# axiom_beta_plugin_module_1xHDMI_v0_6_b41.net
KiCad netlist of a schematic drawn in EAGLE
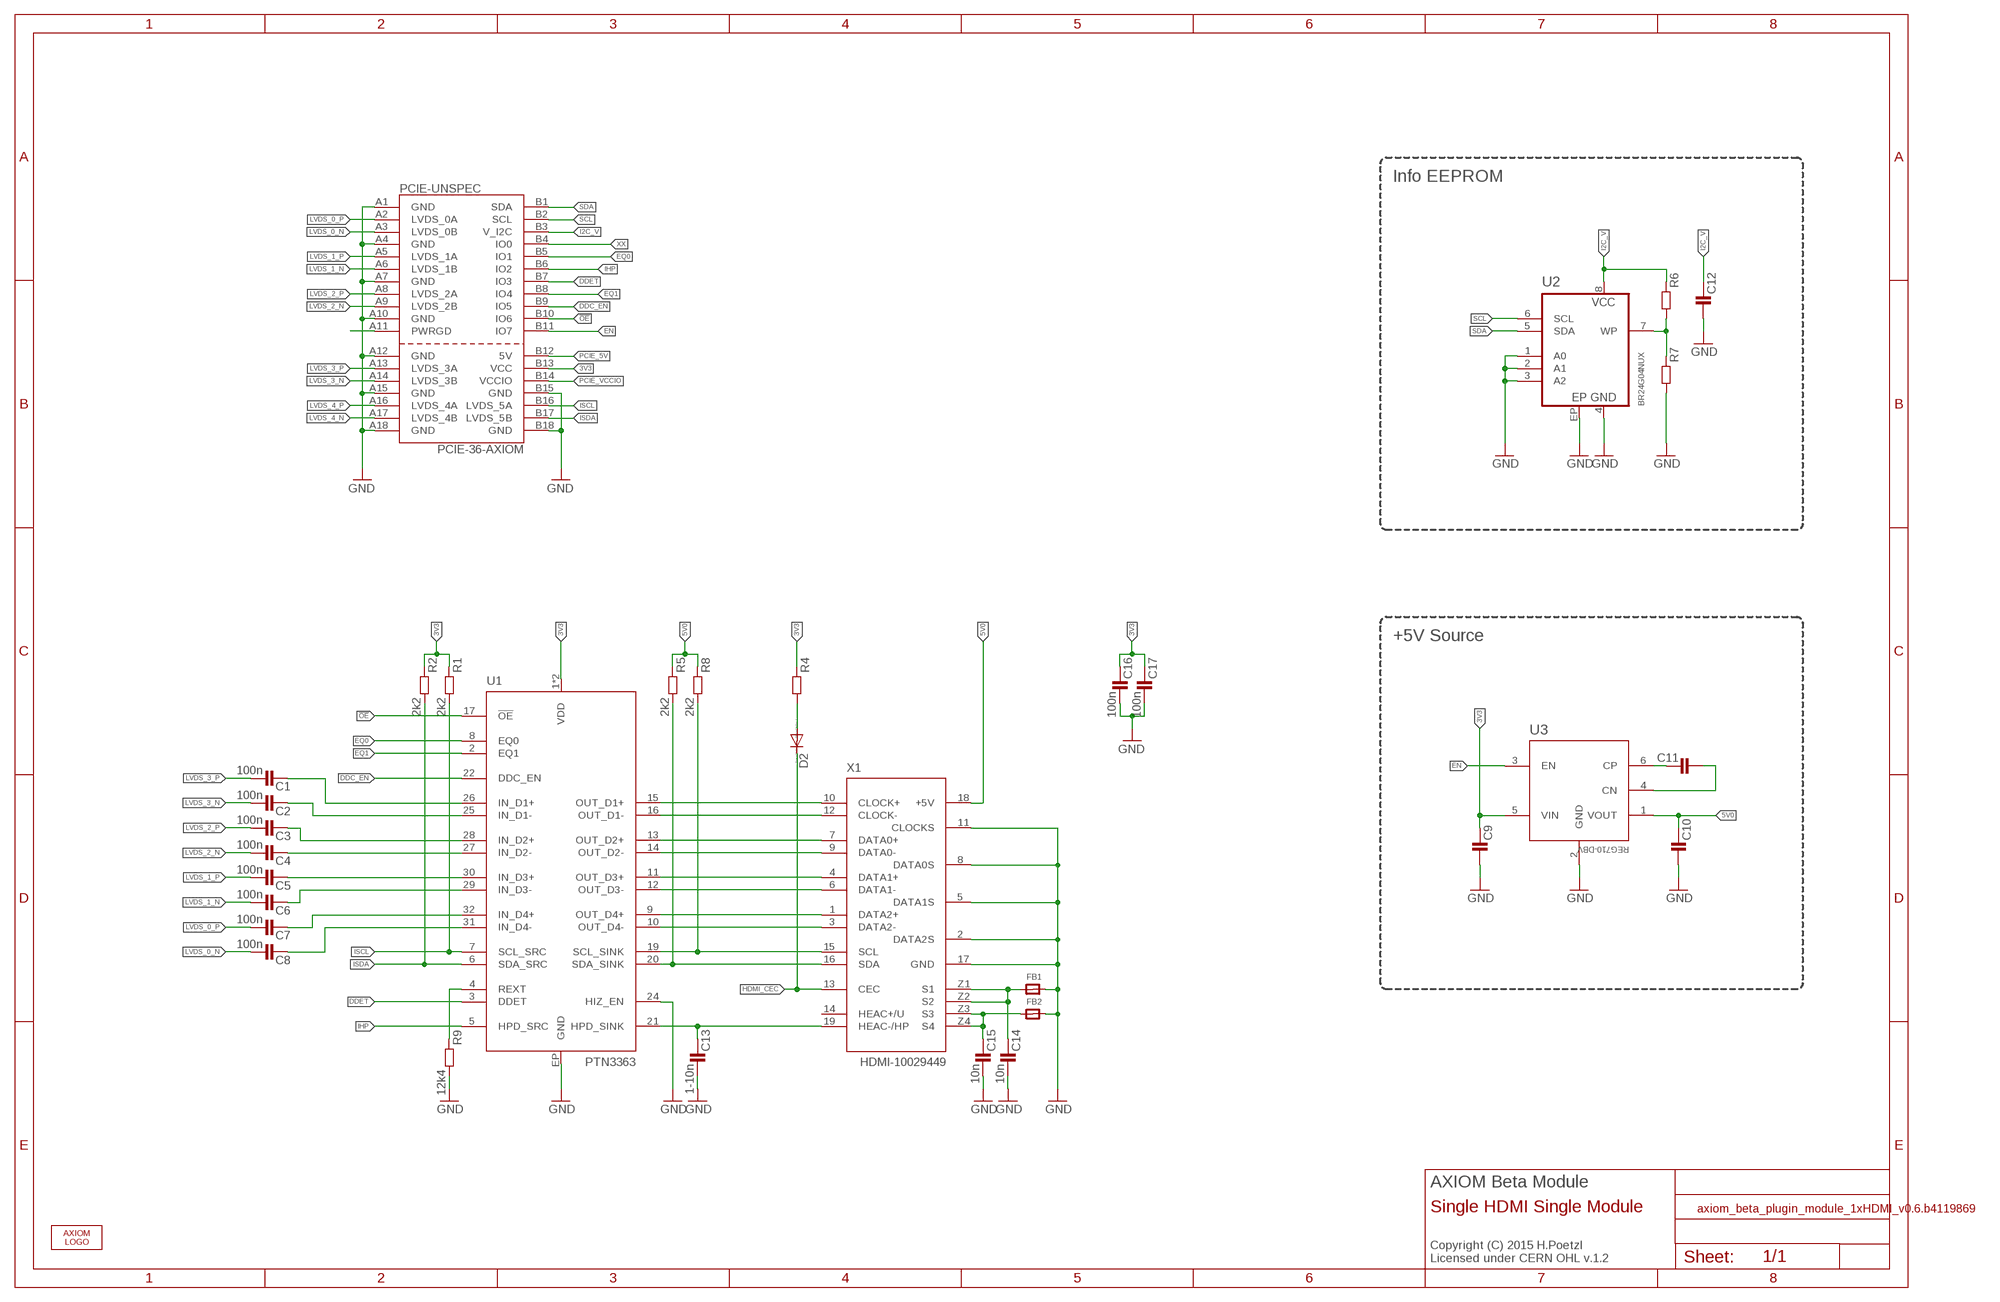
[diagram p0: schematic, sheet 1]

(export (version "E")
  (design (tool "Eeschema 10.0.6"))
  (components
    (comp (ref "C1")
      (value "100n")
      (footprint "eagle-import:0402-C")
      (libsource (lib "eagle-import") (part "C0402-C"))
    )
    (comp (ref "C2")
      (value "100n")
      (footprint "eagle-import:0402-C")
      (libsource (lib "eagle-import") (part "C0402-C"))
    )
    (comp (ref "C3")
      (value "100n")
      (footprint "eagle-import:0402-C")
      (libsource (lib "eagle-import") (part "C0402-C"))
    )
    (comp (ref "C4")
      (value "100n")
      (footprint "eagle-import:0402-C")
      (libsource (lib "eagle-import") (part "C0402-C"))
    )
    (comp (ref "C5")
      (value "100n")
      (footprint "eagle-import:0402-C")
      (libsource (lib "eagle-import") (part "C0402-C"))
    )
    (comp (ref "C6")
      (value "100n")
      (footprint "eagle-import:0402-C")
      (libsource (lib "eagle-import") (part "C0402-C"))
    )
    (comp (ref "C7")
      (value "100n")
      (footprint "eagle-import:0402-C")
      (libsource (lib "eagle-import") (part "C0402-C"))
    )
    (comp (ref "C8")
      (value "100n")
      (footprint "eagle-import:0402-C")
      (libsource (lib "eagle-import") (part "C0402-C"))
    )
    (comp (ref "C9")
      (value "C0603-B")
      (footprint "eagle-import:0603-B")
      (libsource (lib "eagle-import") (part "C0603-B"))
    )
    (comp (ref "C10")
      (value "C0603-B")
      (footprint "eagle-import:0603-B")
      (libsource (lib "eagle-import") (part "C0603-B"))
    )
    (comp (ref "C11")
      (value "C0603-B")
      (footprint "eagle-import:0603-B")
      (libsource (lib "eagle-import") (part "C0603-B"))
    )
    (comp (ref "C12")
      (value "C0402-B")
      (footprint "eagle-import:0402-B")
      (libsource (lib "eagle-import") (part "C0402-B"))
    )
    (comp (ref "C13")
      (value "1-10n")
      (footprint "eagle-import:0402-B")
      (libsource (lib "eagle-import") (part "C0402-B"))
    )
    (comp (ref "C14")
      (value "10n")
      (footprint "eagle-import:0402-B")
      (libsource (lib "eagle-import") (part "C0402-B"))
    )
    (comp (ref "C15")
      (value "10n")
      (footprint "eagle-import:0402-B")
      (libsource (lib "eagle-import") (part "C0402-B"))
    )
    (comp (ref "C16")
      (value "100n")
      (footprint "eagle-import:0402-B")
      (libsource (lib "eagle-import") (part "C0402-B"))
    )
    (comp (ref "C17")
      (value "100n")
      (footprint "eagle-import:0402-B")
      (libsource (lib "eagle-import") (part "C0402-B"))
    )
    (comp (ref "D2")
      (value "DIODE-SOD523")
      (footprint "eagle-import:SOD523")
      (libsource (lib "eagle-import") (part "DIODE-SOD523"))
    )
    (comp (ref "FB1")
      (value "FERRITE_0603MP")
      (footprint "eagle-import:_0603MP")
      (libsource (lib "eagle-import") (part "FERRITE_0603MP"))
    )
    (comp (ref "FB2")
      (value "FERRITE_0603MP")
      (footprint "eagle-import:_0603MP")
      (libsource (lib "eagle-import") (part "FERRITE_0603MP"))
    )
    (comp (ref "PCIE-UNSPEC")
      (value "PCIE-36-AXIOM")
      (footprint "eagle-import:PCIE-36-AXIOM")
      (libsource (lib "eagle-import") (part "PCIE-36-AXIOM"))
    )
    (comp (ref "R1")
      (value "2k2")
      (footprint "eagle-import:0402-B")
      (libsource (lib "eagle-import") (part "R0402-B"))
    )
    (comp (ref "R2")
      (value "2k2")
      (footprint "eagle-import:0402-B")
      (libsource (lib "eagle-import") (part "R0402-B"))
    )
    (comp (ref "R4")
      (value "R0402-B")
      (footprint "eagle-import:0402-B")
      (libsource (lib "eagle-import") (part "R0402-B"))
    )
    (comp (ref "R5")
      (value "2k2")
      (footprint "eagle-import:0402-B")
      (libsource (lib "eagle-import") (part "R0402-B"))
    )
    (comp (ref "R6")
      (value "R0402-B")
      (footprint "eagle-import:0402-B")
      (libsource (lib "eagle-import") (part "R0402-B"))
    )
    (comp (ref "R7")
      (value "R0402-B")
      (footprint "eagle-import:0402-B")
      (libsource (lib "eagle-import") (part "R0402-B"))
    )
    (comp (ref "R8")
      (value "2k2")
      (footprint "eagle-import:0402-B")
      (libsource (lib "eagle-import") (part "R0402-B"))
    )
    (comp (ref "R9")
      (value "12k4")
      (footprint "eagle-import:0402-B")
      (libsource (lib "eagle-import") (part "R0402-B"))
    )
    (comp (ref "U$1")
      (value "AXIOM_LOGO459X70")
      (footprint "eagle-import:AXIOM_LOGO_459X70")
      (libsource (lib "eagle-import") (part "AXIOM_LOGO459X70"))
    )
    (comp (ref "U1")
      (value "PTN3363")
      (footprint "eagle-import:HVQFN32")
      (libsource (lib "eagle-import") (part "PTN3363"))
    )
    (comp (ref "U2")
      (value "BR24G04NUX")
      (footprint "eagle-import:DFN200X300X100-9N")
      (libsource (lib "eagle-import") (part "BR24G04NUX"))
    )
    (comp (ref "U3")
      (value "REG710-DBV")
      (footprint "eagle-import:DBV")
      (libsource (lib "eagle-import") (part "REG710-DBV"))
    )
    (comp (ref "X1")
      (value "HDMI-10029449")
      (footprint "eagle-import:10029449-X01XLF")
      (libsource (lib "eagle-import") (part "HDMI-10029449"))
    )
  )
  (nets
    (net (code "1") (name "/~{OE}") (class "Default")
      (node (ref "PCIE-UNSPEC") (pin "B10") (pinfunction "IO6_B10") (pintype "passive"))
      (node (ref "U1") (pin "17") (pinfunction "~{OE}_17") (pintype "bidirectional"))
    )
    (net (code "2") (name "3V3") (class "Default")
      (node (ref "C16") (pin "1") (pinfunction "1_1") (pintype "passive"))
      (node (ref "C17") (pin "1") (pinfunction "1_1") (pintype "passive"))
      (node (ref "C9") (pin "1") (pinfunction "1_1") (pintype "passive"))
      (node (ref "PCIE-UNSPEC") (pin "B13") (pinfunction "VCC_B13") (pintype "passive"))
      (node (ref "R1") (pin "1") (pinfunction "1_1") (pintype "passive"))
      (node (ref "R2") (pin "1") (pinfunction "1_1") (pintype "passive"))
      (node (ref "R4") (pin "1") (pinfunction "1_1") (pintype "passive"))
      (node (ref "U1") (pin "1") (pinfunction "VDD_1") (pintype "power_in"))
      (node (ref "U1") (pin "18") (pinfunction "VDD_18") (pintype "power_in"))
      (node (ref "U3") (pin "5") (pinfunction "VIN_5") (pintype "power_in"))
    )
    (net (code "3") (name "5V0") (class "Default")
      (node (ref "C10") (pin "1") (pinfunction "1_1") (pintype "passive"))
      (node (ref "R5") (pin "1") (pinfunction "1_1") (pintype "passive"))
      (node (ref "R8") (pin "1") (pinfunction "1_1") (pintype "passive"))
      (node (ref "U3") (pin "1") (pinfunction "VOUT_1") (pintype "output"))
      (node (ref "X1") (pin "18") (pinfunction "+5V_18") (pintype "power_in"))
    )
    (net (code "4") (name "DDC_EN") (class "Default")
      (node (ref "PCIE-UNSPEC") (pin "B9") (pinfunction "IO5_B9") (pintype "passive"))
      (node (ref "U1") (pin "22") (pinfunction "DDC_EN_22") (pintype "bidirectional"))
    )
    (net (code "5") (name "DDET") (class "Default")
      (node (ref "PCIE-UNSPEC") (pin "B7") (pinfunction "IO3_B7") (pintype "passive"))
      (node (ref "U1") (pin "3") (pinfunction "DDET_3") (pintype "bidirectional"))
    )
    (net (code "6") (name "EN") (class "Default")
      (node (ref "PCIE-UNSPEC") (pin "B11") (pinfunction "IO7_B11") (pintype "passive"))
      (node (ref "U3") (pin "3") (pinfunction "EN_3") (pintype "input"))
    )
    (net (code "7") (name "EQ0") (class "Default")
      (node (ref "PCIE-UNSPEC") (pin "B5") (pinfunction "IO1_B5") (pintype "passive"))
      (node (ref "U1") (pin "8") (pinfunction "EQ0_8") (pintype "bidirectional"))
    )
    (net (code "8") (name "EQ1") (class "Default")
      (node (ref "PCIE-UNSPEC") (pin "B8") (pinfunction "IO4_B8") (pintype "passive"))
      (node (ref "U1") (pin "2") (pinfunction "EQ1_2") (pintype "bidirectional"))
    )
    (net (code "9") (name "GND") (class "Default")
      (node (ref "C10") (pin "2") (pinfunction "2_2") (pintype "passive"))
      (node (ref "C12") (pin "2") (pinfunction "2_2") (pintype "passive"))
      (node (ref "C13") (pin "2") (pinfunction "2_2") (pintype "passive"))
      (node (ref "C14") (pin "2") (pinfunction "2_2") (pintype "passive"))
      (node (ref "C15") (pin "2") (pinfunction "2_2") (pintype "passive"))
      (node (ref "C16") (pin "2") (pinfunction "2_2") (pintype "passive"))
      (node (ref "C17") (pin "2") (pinfunction "2_2") (pintype "passive"))
      (node (ref "C9") (pin "2") (pinfunction "2_2") (pintype "passive"))
      (node (ref "FB1") (pin "2") (pinfunction "P$2_2") (pintype "passive"))
      (node (ref "FB2") (pin "2") (pinfunction "P$2_2") (pintype "passive"))
      (node (ref "PCIE-UNSPEC") (pin "A1") (pinfunction "GND_A1") (pintype "passive"))
      (node (ref "PCIE-UNSPEC") (pin "A10") (pinfunction "GND_A10") (pintype "passive"))
      (node (ref "PCIE-UNSPEC") (pin "A12") (pinfunction "GND_A12") (pintype "passive"))
      (node (ref "PCIE-UNSPEC") (pin "A15") (pinfunction "GND_A15") (pintype "passive"))
      (node (ref "PCIE-UNSPEC") (pin "A18") (pinfunction "GND_A18") (pintype "passive"))
      (node (ref "PCIE-UNSPEC") (pin "A4") (pinfunction "GND_A4") (pintype "passive"))
      (node (ref "PCIE-UNSPEC") (pin "A7") (pinfunction "GND_A7") (pintype "passive"))
      (node (ref "PCIE-UNSPEC") (pin "B15") (pinfunction "GND_B15") (pintype "passive"))
      (node (ref "PCIE-UNSPEC") (pin "B18") (pinfunction "GND_B18") (pintype "passive"))
      (node (ref "R7") (pin "2") (pinfunction "2_2") (pintype "passive"))
      (node (ref "R9") (pin "2") (pinfunction "2_2") (pintype "passive"))
      (node (ref "U1") (pin "24") (pinfunction "HIZ_EN_24") (pintype "bidirectional"))
      (node (ref "U1") (pin "EP") (pinfunction "GND_EP") (pintype "bidirectional"))
      (node (ref "U2") (pin "1") (pinfunction "A0_1") (pintype "input"))
      (node (ref "U2") (pin "2") (pinfunction "A1_2") (pintype "input"))
      (node (ref "U2") (pin "3") (pinfunction "A2_3") (pintype "input"))
      (node (ref "U2") (pin "4") (pinfunction "GND_4") (pintype "passive"))
      (node (ref "U2") (pin "EP") (pinfunction "EP_EP") (pintype "passive"))
      (node (ref "U3") (pin "2") (pinfunction "GND_2") (pintype "passive"))
      (node (ref "X1") (pin "11") (pinfunction "CLOCKS_11") (pintype "power_in"))
      (node (ref "X1") (pin "17") (pinfunction "GND_17") (pintype "bidirectional"))
      (node (ref "X1") (pin "2") (pinfunction "DATA2S_2") (pintype "power_in"))
      (node (ref "X1") (pin "5") (pinfunction "DATA1S_5") (pintype "power_in"))
      (node (ref "X1") (pin "8") (pinfunction "DATA0S_8") (pintype "power_in"))
    )
    (net (code "10") (name "HDMI_CEC") (class "Default")
      (node (ref "D2") (pin "C") (pinfunction "C_C") (pintype "passive"))
      (node (ref "X1") (pin "13") (pinfunction "CEC_13") (pintype "bidirectional"))
    )
    (net (code "11") (name "I2C_V") (class "Default")
      (node (ref "C12") (pin "1") (pinfunction "1_1") (pintype "passive"))
      (node (ref "PCIE-UNSPEC") (pin "B3") (pinfunction "V_I2C_B3") (pintype "passive"))
      (node (ref "R6") (pin "1") (pinfunction "1_1") (pintype "passive"))
      (node (ref "U2") (pin "8") (pinfunction "VCC_8") (pintype "power_in"))
    )
    (net (code "12") (name "IHP") (class "Default")
      (node (ref "PCIE-UNSPEC") (pin "B6") (pinfunction "IO2_B6") (pintype "passive"))
      (node (ref "U1") (pin "5") (pinfunction "HPD_SRC_5") (pintype "bidirectional"))
    )
    (net (code "13") (name "ISCL") (class "Default")
      (node (ref "PCIE-UNSPEC") (pin "B16") (pinfunction "LVDS_5A_B16") (pintype "passive"))
      (node (ref "R1") (pin "2") (pinfunction "2_2") (pintype "passive"))
      (node (ref "U1") (pin "7") (pinfunction "SCL_SRC_7") (pintype "bidirectional"))
    )
    (net (code "14") (name "ISDA") (class "Default")
      (node (ref "PCIE-UNSPEC") (pin "B17") (pinfunction "LVDS_5B_B17") (pintype "passive"))
      (node (ref "R2") (pin "2") (pinfunction "2_2") (pintype "passive"))
      (node (ref "U1") (pin "6") (pinfunction "SDA_SRC_6") (pintype "bidirectional"))
    )
    (net (code "15") (name "LVDS_0_N") (class "Default")
      (node (ref "C8") (pin "2") (pinfunction "2_2") (pintype "passive"))
      (node (ref "PCIE-UNSPEC") (pin "A3") (pinfunction "LVDS_0B_A3") (pintype "passive"))
    )
    (net (code "16") (name "LVDS_0_P") (class "Default")
      (node (ref "C7") (pin "2") (pinfunction "2_2") (pintype "passive"))
      (node (ref "PCIE-UNSPEC") (pin "A2") (pinfunction "LVDS_0A_A2") (pintype "passive"))
    )
    (net (code "17") (name "LVDS_1_N") (class "Default")
      (node (ref "C6") (pin "2") (pinfunction "2_2") (pintype "passive"))
      (node (ref "PCIE-UNSPEC") (pin "A6") (pinfunction "LVDS_1B_A6") (pintype "passive"))
    )
    (net (code "18") (name "LVDS_1_P") (class "Default")
      (node (ref "C5") (pin "2") (pinfunction "2_2") (pintype "passive"))
      (node (ref "PCIE-UNSPEC") (pin "A5") (pinfunction "LVDS_1A_A5") (pintype "passive"))
    )
    (net (code "19") (name "LVDS_2_N") (class "Default")
      (node (ref "C4") (pin "2") (pinfunction "2_2") (pintype "passive"))
      (node (ref "PCIE-UNSPEC") (pin "A9") (pinfunction "LVDS_2B_A9") (pintype "passive"))
    )
    (net (code "20") (name "LVDS_2_P") (class "Default")
      (node (ref "C3") (pin "2") (pinfunction "2_2") (pintype "passive"))
      (node (ref "PCIE-UNSPEC") (pin "A8") (pinfunction "LVDS_2A_A8") (pintype "passive"))
    )
    (net (code "21") (name "LVDS_3_N") (class "Default")
      (node (ref "C2") (pin "2") (pinfunction "2_2") (pintype "passive"))
      (node (ref "PCIE-UNSPEC") (pin "A14") (pinfunction "LVDS_3B_A14") (pintype "passive"))
    )
    (net (code "22") (name "LVDS_3_P") (class "Default")
      (node (ref "C1") (pin "2") (pinfunction "2_2") (pintype "passive"))
      (node (ref "PCIE-UNSPEC") (pin "A13") (pinfunction "LVDS_3A_A13") (pintype "passive"))
    )
    (net (code "23") (name "LVDS_4_N") (class "Default")
      (node (ref "PCIE-UNSPEC") (pin "A17") (pinfunction "LVDS_4B_A17") (pintype "passive"))
    )
    (net (code "24") (name "LVDS_4_P") (class "Default")
      (node (ref "PCIE-UNSPEC") (pin "A16") (pinfunction "LVDS_4A_A16") (pintype "passive"))
    )
    (net (code "25") (name "Net-(D2-PadA)") (class "Default")
      (node (ref "D2") (pin "A") (pinfunction "A_A") (pintype "passive"))
      (node (ref "R4") (pin "2") (pinfunction "2_2") (pintype "passive"))
    )
    (net (code "26") (name "Net-(FB1-P$1)") (class "Default")
      (node (ref "C14") (pin "1") (pinfunction "1_1") (pintype "passive"))
      (node (ref "FB1") (pin "1") (pinfunction "P$1_1") (pintype "passive"))
      (node (ref "X1") (pin "Z1") (pinfunction "S1_Z1") (pintype "power_in"))
      (node (ref "X1") (pin "Z2") (pinfunction "S2_Z2") (pintype "power_in"))
    )
    (net (code "27") (name "Net-(FB2-P$1)") (class "Default")
      (node (ref "C15") (pin "1") (pinfunction "1_1") (pintype "passive"))
      (node (ref "FB2") (pin "1") (pinfunction "P$1_1") (pintype "passive"))
      (node (ref "X1") (pin "Z3") (pinfunction "S3_Z3") (pintype "power_in"))
      (node (ref "X1") (pin "Z4") (pinfunction "S4_Z4") (pintype "power_in"))
    )
    (net (code "28") (name "Net-(U1-HPD_SINK)") (class "Default")
      (node (ref "C13") (pin "1") (pinfunction "1_1") (pintype "passive"))
      (node (ref "U1") (pin "21") (pinfunction "HPD_SINK_21") (pintype "bidirectional"))
      (node (ref "X1") (pin "19") (pinfunction "HEAC-/HP_19") (pintype "bidirectional"))
    )
    (net (code "29") (name "Net-(U1-IN_D1+)") (class "Default")
      (node (ref "C1") (pin "1") (pinfunction "1_1") (pintype "passive"))
      (node (ref "U1") (pin "26") (pinfunction "IN_D1+_26") (pintype "bidirectional"))
    )
    (net (code "30") (name "Net-(U1-IN_D1-)") (class "Default")
      (node (ref "C2") (pin "1") (pinfunction "1_1") (pintype "passive"))
      (node (ref "U1") (pin "25") (pinfunction "IN_D1-_25") (pintype "bidirectional"))
    )
    (net (code "31") (name "Net-(U1-IN_D2+)") (class "Default")
      (node (ref "C3") (pin "1") (pinfunction "1_1") (pintype "passive"))
      (node (ref "U1") (pin "28") (pinfunction "IN_D2+_28") (pintype "bidirectional"))
    )
    (net (code "32") (name "Net-(U1-IN_D2-)") (class "Default")
      (node (ref "C4") (pin "1") (pinfunction "1_1") (pintype "passive"))
      (node (ref "U1") (pin "27") (pinfunction "IN_D2-_27") (pintype "bidirectional"))
    )
    (net (code "33") (name "Net-(U1-IN_D3+)") (class "Default")
      (node (ref "C5") (pin "1") (pinfunction "1_1") (pintype "passive"))
      (node (ref "U1") (pin "30") (pinfunction "IN_D3+_30") (pintype "bidirectional"))
    )
    (net (code "34") (name "Net-(U1-IN_D3-)") (class "Default")
      (node (ref "C6") (pin "1") (pinfunction "1_1") (pintype "passive"))
      (node (ref "U1") (pin "29") (pinfunction "IN_D3-_29") (pintype "bidirectional"))
    )
    (net (code "35") (name "Net-(U1-IN_D4+)") (class "Default")
      (node (ref "C7") (pin "1") (pinfunction "1_1") (pintype "passive"))
      (node (ref "U1") (pin "32") (pinfunction "IN_D4+_32") (pintype "bidirectional"))
    )
    (net (code "36") (name "Net-(U1-IN_D4-)") (class "Default")
      (node (ref "C8") (pin "1") (pinfunction "1_1") (pintype "passive"))
      (node (ref "U1") (pin "31") (pinfunction "IN_D4-_31") (pintype "bidirectional"))
    )
    (net (code "37") (name "Net-(U1-OUT_D1+)") (class "Default")
      (node (ref "U1") (pin "15") (pinfunction "OUT_D1+_15") (pintype "bidirectional"))
      (node (ref "X1") (pin "10") (pinfunction "CLOCK+_10") (pintype "bidirectional"))
    )
    (net (code "38") (name "Net-(U1-OUT_D1-)") (class "Default")
      (node (ref "U1") (pin "16") (pinfunction "OUT_D1-_16") (pintype "bidirectional"))
      (node (ref "X1") (pin "12") (pinfunction "CLOCK-_12") (pintype "bidirectional"))
    )
    (net (code "39") (name "Net-(U1-OUT_D2+)") (class "Default")
      (node (ref "U1") (pin "13") (pinfunction "OUT_D2+_13") (pintype "bidirectional"))
      (node (ref "X1") (pin "7") (pinfunction "DATA0+_7") (pintype "bidirectional"))
    )
    (net (code "40") (name "Net-(U1-OUT_D2-)") (class "Default")
      (node (ref "U1") (pin "14") (pinfunction "OUT_D2-_14") (pintype "bidirectional"))
      (node (ref "X1") (pin "9") (pinfunction "DATA0-_9") (pintype "bidirectional"))
    )
    (net (code "41") (name "Net-(U1-OUT_D3+)") (class "Default")
      (node (ref "U1") (pin "11") (pinfunction "OUT_D3+_11") (pintype "bidirectional"))
      (node (ref "X1") (pin "4") (pinfunction "DATA1+_4") (pintype "bidirectional"))
    )
    (net (code "42") (name "Net-(U1-OUT_D3-)") (class "Default")
      (node (ref "U1") (pin "12") (pinfunction "OUT_D3-_12") (pintype "bidirectional"))
      (node (ref "X1") (pin "6") (pinfunction "DATA1-_6") (pintype "bidirectional"))
    )
    (net (code "43") (name "Net-(U1-OUT_D4+)") (class "Default")
      (node (ref "U1") (pin "9") (pinfunction "OUT_D4+_9") (pintype "bidirectional"))
      (node (ref "X1") (pin "1") (pinfunction "DATA2+_1") (pintype "bidirectional"))
    )
    (net (code "44") (name "Net-(U1-OUT_D4-)") (class "Default")
      (node (ref "U1") (pin "10") (pinfunction "OUT_D4-_10") (pintype "bidirectional"))
      (node (ref "X1") (pin "3") (pinfunction "DATA2-_3") (pintype "bidirectional"))
    )
    (net (code "45") (name "Net-(U1-REXT)") (class "Default")
      (node (ref "R9") (pin "1") (pinfunction "1_1") (pintype "passive"))
      (node (ref "U1") (pin "4") (pinfunction "REXT_4") (pintype "bidirectional"))
    )
    (net (code "46") (name "Net-(U1-SCL_SINK)") (class "Default")
      (node (ref "R8") (pin "2") (pinfunction "2_2") (pintype "passive"))
      (node (ref "U1") (pin "19") (pinfunction "SCL_SINK_19") (pintype "bidirectional"))
      (node (ref "X1") (pin "15") (pinfunction "SCL_15") (pintype "bidirectional"))
    )
    (net (code "47") (name "Net-(U1-SDA_SINK)") (class "Default")
      (node (ref "R5") (pin "2") (pinfunction "2_2") (pintype "passive"))
      (node (ref "U1") (pin "20") (pinfunction "SDA_SINK_20") (pintype "bidirectional"))
      (node (ref "X1") (pin "16") (pinfunction "SDA_16") (pintype "bidirectional"))
    )
    (net (code "48") (name "Net-(U2-WP)") (class "Default")
      (node (ref "R6") (pin "2") (pinfunction "2_2") (pintype "passive"))
      (node (ref "R7") (pin "1") (pinfunction "1_1") (pintype "passive"))
      (node (ref "U2") (pin "7") (pinfunction "WP_7") (pintype "input"))
    )
    (net (code "49") (name "Net-(U3-CN)") (class "Default")
      (node (ref "C11") (pin "2") (pinfunction "2_2") (pintype "passive"))
      (node (ref "U3") (pin "4") (pinfunction "CN_4") (pintype "power_in"))
    )
    (net (code "50") (name "Net-(U3-CP)") (class "Default")
      (node (ref "C11") (pin "1") (pinfunction "1_1") (pintype "passive"))
      (node (ref "U3") (pin "6") (pinfunction "CP_6") (pintype "output"))
    )
    (net (code "51") (name "PCIE_5V") (class "Default")
      (node (ref "PCIE-UNSPEC") (pin "B12") (pinfunction "5V_B12") (pintype "passive"))
    )
    (net (code "52") (name "PCIE_VCCIO") (class "Default")
      (node (ref "PCIE-UNSPEC") (pin "B14") (pinfunction "VCCIO_B14") (pintype "passive"))
    )
    (net (code "53") (name "SCL") (class "Default")
      (node (ref "PCIE-UNSPEC") (pin "B2") (pinfunction "SCL_B2") (pintype "passive"))
      (node (ref "U2") (pin "6") (pinfunction "SCL_6") (pintype "input"))
    )
    (net (code "54") (name "SDA") (class "Default")
      (node (ref "PCIE-UNSPEC") (pin "B1") (pinfunction "SDA_B1") (pintype "passive"))
      (node (ref "U2") (pin "5") (pinfunction "SDA_5") (pintype "bidirectional"))
    )
    (net (code "55") (name "XX") (class "Default")
      (node (ref "PCIE-UNSPEC") (pin "B4") (pinfunction "IO0_B4") (pintype "passive"))
    )
    (net (code "56") (name "unconnected-(PCIE-UNSPEC-PWRGD-PadA11)") (class "Default")
      (node (ref "PCIE-UNSPEC") (pin "A11") (pinfunction "PWRGD_A11") (pintype "passive"))
    )
    (net (code "57") (name "unconnected-(X1-HEAC+{slash}U-Pad14)") (class "Default")
      (node (ref "X1") (pin "14") (pinfunction "HEAC+/U_14") (pintype "bidirectional"))
    )
  )
)
